# AnalogSense.net
KiCad netlist of a schematic drawn in Altium Designer
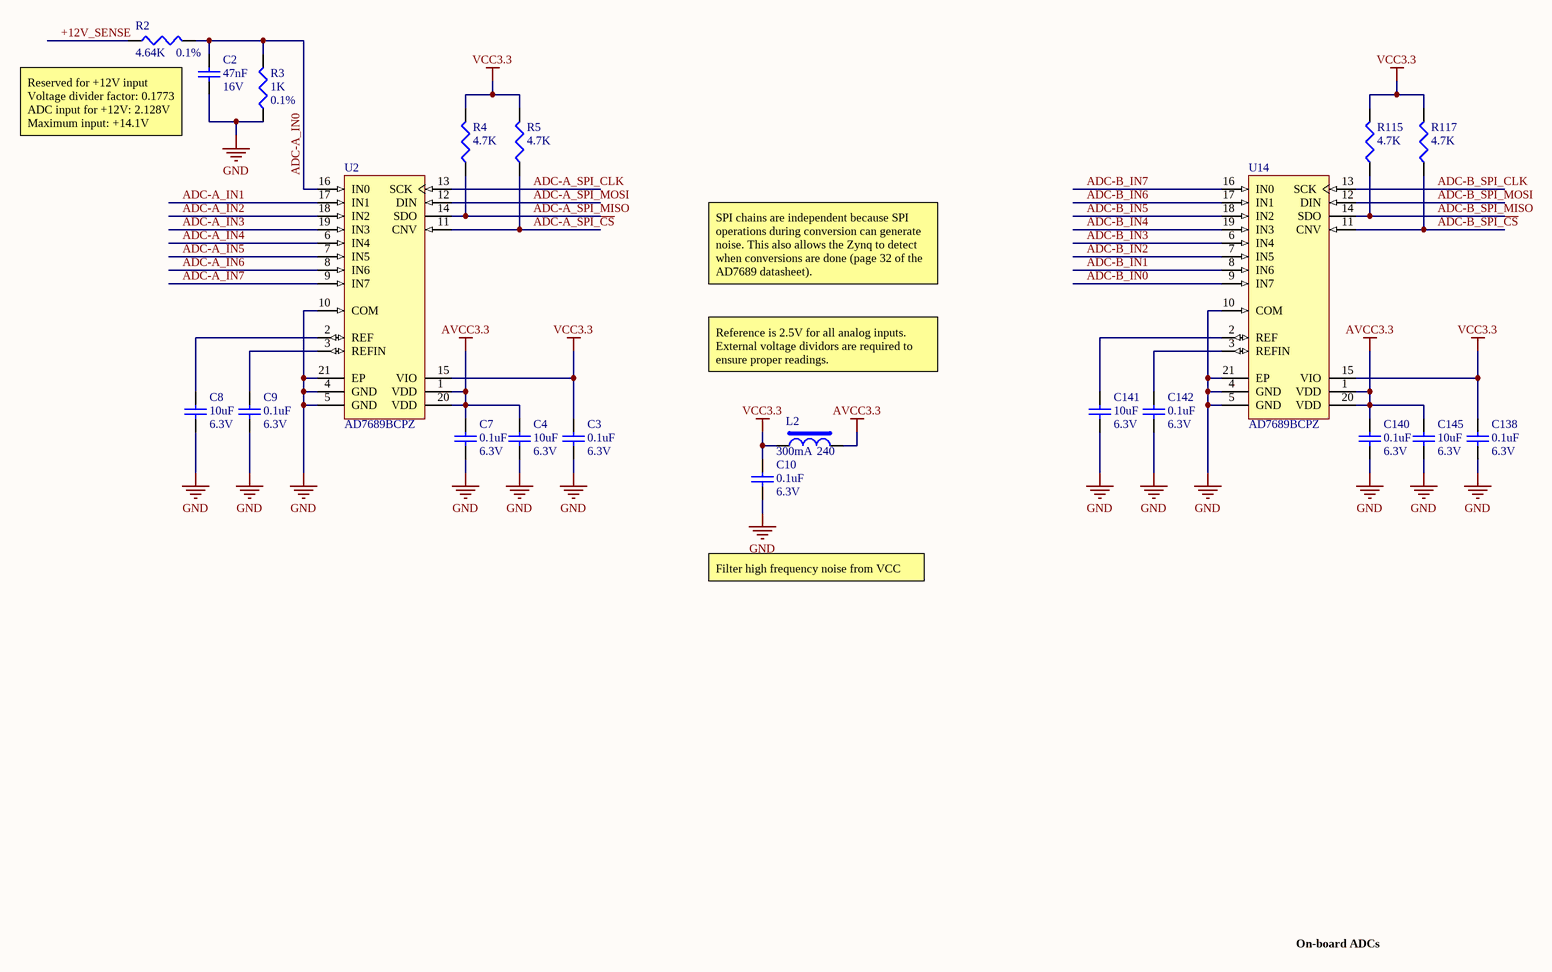
[diagram p0: AnalogSense.SchDoc]

(export (version "E")
  (design (tool "Eeschema 10.0.6"))
  (components
    (comp (ref "C2")
      (value "47nF")
      (footprint "C0402_IPC_H")
      (description "Capacitor")
      (fields
        (field (name "RATING") "16V")
        (field (name "PART") "GRM155R71C473KA01D")
        (field (name "MANUFACTURER") "Murata")
      )
      (libsource (lib "CustomParts") (part "Cap"))
    )
    (comp (ref "C3")
      (value "0.1uF")
      (footprint "C0201_IPC_H")
      (description "Capacitor")
      (fields
        (field (name "RATING") "6.3V")
        (field (name "MANUFACTURER") "Murata")
        (field (name "PART") "GRM033R60J104KE19D")
      )
      (libsource (lib "CustomParts") (part "Cap"))
    )
    (comp (ref "C4")
      (value "10uF")
      (footprint "C0402_IPC_H")
      (description "Capacitor")
      (fields
        (field (name "RATING") "6.3V")
        (field (name "MANUFACTURER") "Murata")
        (field (name "PART") "GRM155R60J106ME44D")
      )
      (libsource (lib "CustomParts") (part "Cap"))
    )
    (comp (ref "C7")
      (value "0.1uF")
      (footprint "C0201_IPC_H")
      (description "Capacitor")
      (fields
        (field (name "RATING") "6.3V")
        (field (name "MANUFACTURER") "Murata")
        (field (name "PART") "GRM033R60J104KE19D")
      )
      (libsource (lib "CustomParts") (part "Cap"))
    )
    (comp (ref "C8")
      (value "10uF")
      (footprint "C0402_IPC_H")
      (description "Capacitor")
      (fields
        (field (name "RATING") "6.3V")
        (field (name "MANUFACTURER") "Murata")
        (field (name "PART") "GRM155R60J106ME44D")
      )
      (libsource (lib "CustomParts") (part "Cap"))
    )
    (comp (ref "C9")
      (value "0.1uF")
      (footprint "C0201_IPC_H")
      (description "Capacitor")
      (fields
        (field (name "RATING") "6.3V")
        (field (name "MANUFACTURER") "Murata")
        (field (name "PART") "GRM033R60J104KE19D")
      )
      (libsource (lib "CustomParts") (part "Cap"))
    )
    (comp (ref "C10")
      (value "0.1uF")
      (footprint "C0201_IPC_H")
      (description "Capacitor")
      (fields
        (field (name "RATING") "6.3V")
        (field (name "MANUFACTURER") "Murata")
        (field (name "PART") "GRM033R60J104KE19D")
      )
      (libsource (lib "CustomParts") (part "Cap"))
    )
    (comp (ref "C138")
      (value "0.1uF")
      (footprint "C0201_IPC_H")
      (description "Capacitor")
      (fields
        (field (name "RATING") "6.3V")
        (field (name "MANUFACTURER") "Murata")
        (field (name "PART") "GRM033R60J104KE19D")
      )
      (libsource (lib "CustomParts") (part "Cap"))
    )
    (comp (ref "C140")
      (value "0.1uF")
      (footprint "C0201_IPC_H")
      (description "Capacitor")
      (fields
        (field (name "RATING") "6.3V")
        (field (name "MANUFACTURER") "Murata")
        (field (name "PART") "GRM033R60J104KE19D")
      )
      (libsource (lib "CustomParts") (part "Cap"))
    )
    (comp (ref "C141")
      (value "10uF")
      (footprint "C0402_IPC_H")
      (description "Capacitor")
      (fields
        (field (name "RATING") "6.3V")
        (field (name "MANUFACTURER") "Murata")
        (field (name "PART") "GRM155R60J106ME44D")
      )
      (libsource (lib "CustomParts") (part "Cap"))
    )
    (comp (ref "C142")
      (value "0.1uF")
      (footprint "C0201_IPC_H")
      (description "Capacitor")
      (fields
        (field (name "RATING") "6.3V")
        (field (name "MANUFACTURER") "Murata")
        (field (name "PART") "GRM033R60J104KE19D")
      )
      (libsource (lib "CustomParts") (part "Cap"))
    )
    (comp (ref "C145")
      (value "10uF")
      (footprint "C0402_IPC_H")
      (description "Capacitor")
      (fields
        (field (name "RATING") "6.3V")
        (field (name "MANUFACTURER") "Murata")
        (field (name "PART") "GRM155R60J106ME44D")
      )
      (libsource (lib "CustomParts") (part "Cap"))
    )
    (comp (ref "L2")
      (value "240")
      (footprint "L0402_H")
      (description "Bead Inductor")
      (fields
        (field (name "RATED CURRENT") "300mA")
        (field (name "MANUFACTURER") "Taiyo Yuden")
        (field (name "PART") "BK1005HM241-T")
      )
      (libsource (lib "CustomParts") (part "Bead"))
    )
    (comp (ref "R2")
      (value "4.64K")
      (footprint "R0603")
      (description "Resistor")
      (fields
        (field (name "TOLERANCE") "0.1%")
        (field (name "MANUFACTURER") "Susumu Co Ltd")
        (field (name "PART") "RG1608P-4641-B-T1")
      )
      (libsource (lib "CustomParts") (part "Res"))
    )
    (comp (ref "R3")
      (value "1K")
      (footprint "R0402_IPC_H")
      (description "Resistor")
      (fields
        (field (name "TOLERANCE") "0.1%")
        (field (name "MANUFACTURER") "Vishay")
        (field (name "PART") "TNPW04021K00BEED")
      )
      (libsource (lib "CustomParts") (part "Res"))
    )
    (comp (ref "R4")
      (value "4.7K")
      (footprint "R0402_IPC_H")
      (description "Resistor")
      (fields (field (name "TOLERANCE") "1%") (field (name "MANUFACTURER") "Panasonic"))
      (libsource (lib "CustomParts") (part "Res"))
    )
    (comp (ref "R5")
      (value "4.7K")
      (footprint "R0402_IPC_H")
      (description "Resistor")
      (fields (field (name "TOLERANCE") "1%") (field (name "MANUFACTURER") "Panasonic"))
      (libsource (lib "CustomParts") (part "Res"))
    )
    (comp (ref "R115")
      (value "4.7K")
      (footprint "R0402_IPC_H")
      (description "Resistor")
      (fields (field (name "TOLERANCE") "1%") (field (name "MANUFACTURER") "Panasonic"))
      (libsource (lib "CustomParts") (part "Res"))
    )
    (comp (ref "R117")
      (value "4.7K")
      (footprint "R0402_IPC_H")
      (description "Resistor")
      (fields (field (name "TOLERANCE") "1%") (field (name "MANUFACTURER") "Panasonic"))
      (libsource (lib "CustomParts") (part "Res"))
    )
    (comp (ref "U2")
      (value "AD7689BCPZ")
      (footprint "CP-20-4_N")
      (fields (field (name "GENERIC PART NUMBER") "AD7689") (field (name "MANUFACTURER") "Analog"))
      (libsource (lib "altium-import") (part "root_0_mirrored_CMP-0313-00576-2_"))
    )
    (comp (ref "U14")
      (value "AD7689BCPZ")
      (footprint "CP-20-4_N")
      (fields (field (name "GENERIC PART NUMBER") "AD7689") (field (name "MANUFACTURER") "Analog"))
      (libsource (lib "altium-import") (part "root_0_mirrored_CMP-0313-00576-2_"))
    )
  )
  (nets
    (net (code "1") (name "/+12V_SENSE") (class "Default")
      (node (ref "R2") (pin "1") (pinfunction "1_1") (pintype "passive"))
    )
    (net (code "2") (name "/ADC-A_IN0") (class "Default")
      (node (ref "C2") (pin "2") (pinfunction "2_2") (pintype "passive"))
      (node (ref "R2") (pin "2") (pinfunction "2_2") (pintype "passive"))
      (node (ref "R3") (pin "2") (pinfunction "2_2") (pintype "passive"))
      (node (ref "U2") (pin "16") (pinfunction "IN0_16") (pintype "input"))
    )
    (net (code "3") (name "/ADC-A_IN1") (class "Default")
      (node (ref "U2") (pin "17") (pinfunction "IN1_17") (pintype "input"))
    )
    (net (code "4") (name "/ADC-A_IN2") (class "Default")
      (node (ref "U2") (pin "18") (pinfunction "IN2_18") (pintype "input"))
    )
    (net (code "5") (name "/ADC-A_IN3") (class "Default")
      (node (ref "U2") (pin "19") (pinfunction "IN3_19") (pintype "input"))
    )
    (net (code "6") (name "/ADC-A_IN4") (class "Default")
      (node (ref "U2") (pin "6") (pinfunction "IN4_6") (pintype "input"))
    )
    (net (code "7") (name "/ADC-A_IN5") (class "Default")
      (node (ref "U2") (pin "7") (pinfunction "IN5_7") (pintype "input"))
    )
    (net (code "8") (name "/ADC-A_IN6") (class "Default")
      (node (ref "U2") (pin "8") (pinfunction "IN6_8") (pintype "input"))
    )
    (net (code "9") (name "/ADC-A_IN7") (class "Default")
      (node (ref "U2") (pin "9") (pinfunction "IN7_9") (pintype "input"))
    )
    (net (code "10") (name "/ADC-A_SPI_CLK") (class "Default")
      (node (ref "U2") (pin "13") (pinfunction "SCK_13") (pintype "input"))
    )
    (net (code "11") (name "/ADC-A_SPI_CS") (class "Default")
      (node (ref "R5") (pin "1") (pinfunction "1_1") (pintype "passive"))
      (node (ref "U2") (pin "11") (pinfunction "CNV_11") (pintype "input"))
    )
    (net (code "12") (name "/ADC-A_SPI_MISO") (class "Default")
      (node (ref "R4") (pin "1") (pinfunction "1_1") (pintype "passive"))
      (node (ref "U2") (pin "14") (pinfunction "SDO_14") (pintype "tri_state"))
    )
    (net (code "13") (name "/ADC-A_SPI_MOSI") (class "Default")
      (node (ref "U2") (pin "12") (pinfunction "DIN_12") (pintype "input"))
    )
    (net (code "14") (name "/ADC-B_IN0") (class "Default")
      (node (ref "U14") (pin "9") (pinfunction "IN7_9") (pintype "input"))
    )
    (net (code "15") (name "/ADC-B_IN1") (class "Default")
      (node (ref "U14") (pin "8") (pinfunction "IN6_8") (pintype "input"))
    )
    (net (code "16") (name "/ADC-B_IN2") (class "Default")
      (node (ref "U14") (pin "7") (pinfunction "IN5_7") (pintype "input"))
    )
    (net (code "17") (name "/ADC-B_IN3") (class "Default")
      (node (ref "U14") (pin "6") (pinfunction "IN4_6") (pintype "input"))
    )
    (net (code "18") (name "/ADC-B_IN4") (class "Default")
      (node (ref "U14") (pin "19") (pinfunction "IN3_19") (pintype "input"))
    )
    (net (code "19") (name "/ADC-B_IN5") (class "Default")
      (node (ref "U14") (pin "18") (pinfunction "IN2_18") (pintype "input"))
    )
    (net (code "20") (name "/ADC-B_IN6") (class "Default")
      (node (ref "U14") (pin "17") (pinfunction "IN1_17") (pintype "input"))
    )
    (net (code "21") (name "/ADC-B_IN7") (class "Default")
      (node (ref "U14") (pin "16") (pinfunction "IN0_16") (pintype "input"))
    )
    (net (code "22") (name "/ADC-B_SPI_CLK") (class "Default")
      (node (ref "U14") (pin "13") (pinfunction "SCK_13") (pintype "input"))
    )
    (net (code "23") (name "/ADC-B_SPI_CS") (class "Default")
      (node (ref "R117") (pin "1") (pinfunction "1_1") (pintype "passive"))
      (node (ref "U14") (pin "11") (pinfunction "CNV_11") (pintype "input"))
    )
    (net (code "24") (name "/ADC-B_SPI_MISO") (class "Default")
      (node (ref "R115") (pin "1") (pinfunction "1_1") (pintype "passive"))
      (node (ref "U14") (pin "14") (pinfunction "SDO_14") (pintype "tri_state"))
    )
    (net (code "25") (name "/ADC-B_SPI_MOSI") (class "Default")
      (node (ref "U14") (pin "12") (pinfunction "DIN_12") (pintype "input"))
    )
    (net (code "26") (name "AVCC3.3") (class "Default")
      (node (ref "C140") (pin "2") (pinfunction "2_2") (pintype "passive"))
      (node (ref "C145") (pin "2") (pinfunction "2_2") (pintype "passive"))
      (node (ref "C4") (pin "2") (pinfunction "2_2") (pintype "passive"))
      (node (ref "C7") (pin "2") (pinfunction "2_2") (pintype "passive"))
      (node (ref "L2") (pin "2") (pinfunction "2_2") (pintype "passive"))
      (node (ref "U14") (pin "1") (pinfunction "VDD_1") (pintype "power_in"))
      (node (ref "U14") (pin "20") (pinfunction "VDD_20") (pintype "power_in"))
      (node (ref "U2") (pin "1") (pinfunction "VDD_1") (pintype "power_in"))
      (node (ref "U2") (pin "20") (pinfunction "VDD_20") (pintype "power_in"))
    )
    (net (code "27") (name "GND") (class "Default")
      (node (ref "C10") (pin "1") (pinfunction "1_1") (pintype "passive"))
      (node (ref "C138") (pin "1") (pinfunction "1_1") (pintype "passive"))
      (node (ref "C140") (pin "1") (pinfunction "1_1") (pintype "passive"))
      (node (ref "C141") (pin "1") (pinfunction "1_1") (pintype "passive"))
      (node (ref "C142") (pin "1") (pinfunction "1_1") (pintype "passive"))
      (node (ref "C145") (pin "1") (pinfunction "1_1") (pintype "passive"))
      (node (ref "C2") (pin "1") (pinfunction "1_1") (pintype "passive"))
      (node (ref "C3") (pin "1") (pinfunction "1_1") (pintype "passive"))
      (node (ref "C4") (pin "1") (pinfunction "1_1") (pintype "passive"))
      (node (ref "C7") (pin "1") (pinfunction "1_1") (pintype "passive"))
      (node (ref "C8") (pin "1") (pinfunction "1_1") (pintype "passive"))
      (node (ref "C9") (pin "1") (pinfunction "1_1") (pintype "passive"))
      (node (ref "R3") (pin "1") (pinfunction "1_1") (pintype "passive"))
      (node (ref "U14") (pin "10") (pinfunction "COM_10") (pintype "input"))
      (node (ref "U14") (pin "21") (pinfunction "EP_21") (pintype "power_in"))
      (node (ref "U14") (pin "4") (pinfunction "GND_4") (pintype "power_in"))
      (node (ref "U14") (pin "5") (pinfunction "GND_5") (pintype "power_in"))
      (node (ref "U2") (pin "10") (pinfunction "COM_10") (pintype "input"))
      (node (ref "U2") (pin "21") (pinfunction "EP_21") (pintype "power_in"))
      (node (ref "U2") (pin "4") (pinfunction "GND_4") (pintype "power_in"))
      (node (ref "U2") (pin "5") (pinfunction "GND_5") (pintype "power_in"))
    )
    (net (code "28") (name "Net-(U2-REF)") (class "Default")
      (node (ref "C8") (pin "2") (pinfunction "2_2") (pintype "passive"))
      (node (ref "U2") (pin "2") (pinfunction "REF_2") (pintype "bidirectional"))
    )
    (net (code "29") (name "Net-(U2-REFIN)") (class "Default")
      (node (ref "C9") (pin "2") (pinfunction "2_2") (pintype "passive"))
      (node (ref "U2") (pin "3") (pinfunction "REFIN_3") (pintype "bidirectional"))
    )
    (net (code "30") (name "Net-(U14-REF)") (class "Default")
      (node (ref "C141") (pin "2") (pinfunction "2_2") (pintype "passive"))
      (node (ref "U14") (pin "2") (pinfunction "REF_2") (pintype "bidirectional"))
    )
    (net (code "31") (name "Net-(U14-REFIN)") (class "Default")
      (node (ref "C142") (pin "2") (pinfunction "2_2") (pintype "passive"))
      (node (ref "U14") (pin "3") (pinfunction "REFIN_3") (pintype "bidirectional"))
    )
    (net (code "32") (name "VCC3.3") (class "Default")
      (node (ref "C10") (pin "2") (pinfunction "2_2") (pintype "passive"))
      (node (ref "C138") (pin "2") (pinfunction "2_2") (pintype "passive"))
      (node (ref "C3") (pin "2") (pinfunction "2_2") (pintype "passive"))
      (node (ref "L2") (pin "1") (pinfunction "1_1") (pintype "passive"))
      (node (ref "R115") (pin "2") (pinfunction "2_2") (pintype "passive"))
      (node (ref "R117") (pin "2") (pinfunction "2_2") (pintype "passive"))
      (node (ref "R4") (pin "2") (pinfunction "2_2") (pintype "passive"))
      (node (ref "R5") (pin "2") (pinfunction "2_2") (pintype "passive"))
      (node (ref "U14") (pin "15") (pinfunction "VIO_15") (pintype "power_in"))
      (node (ref "U2") (pin "15") (pinfunction "VIO_15") (pintype "power_in"))
    )
  )
)
